# ext_rgb_M.net
KiCad netlist of a schematic drawn in EAGLE
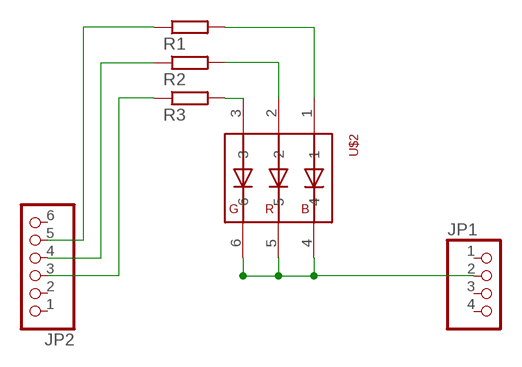
[diagram p0: schematic, sheet 1]

(export (version "E")
  (design (tool "Eeschema 10.0.6"))
  (components
    (comp (ref "JP1")
      (value "PINHD-1X4")
      (footprint "eagle-import:1X04")
      (libsource (lib "eagle-import") (part "PINHD-1X4"))
    )
    (comp (ref "JP2")
      (value "PINHD-1X6")
      (footprint "eagle-import:1X06")
      (libsource (lib "eagle-import") (part "PINHD-1X6"))
    )
    (comp (ref "R1")
      (value "R-EU_R0603")
      (footprint "eagle-import:R0603")
      (libsource (lib "eagle-import") (part "R-EU_R0603"))
    )
    (comp (ref "R2")
      (value "R-EU_R0603")
      (footprint "eagle-import:R0603")
      (libsource (lib "eagle-import") (part "R-EU_R0603"))
    )
    (comp (ref "R3")
      (value "R-EU_R0603")
      (footprint "eagle-import:R0603")
      (libsource (lib "eagle-import") (part "R-EU_R0603"))
    )
    (comp (ref "U$2")
      (value "RGB_WW-FCE50TC-Q1")
      (footprint "eagle-import:RGB_WW-FCE50TC-Q1")
      (libsource (lib "eagle-import") (part "RGB_WW-FCE50TC-Q1"))
    )
  )
  (nets
    (net (code "1") (name "Net-(JP1-Pad2)") (class "Default")
      (node (ref "JP1") (pin "2") (pinfunction "2_2") (pintype "passive"))
      (node (ref "U$2") (pin "4") (pinfunction "4_4") (pintype "bidirectional"))
      (node (ref "U$2") (pin "5") (pinfunction "5_5") (pintype "bidirectional"))
      (node (ref "U$2") (pin "6") (pinfunction "6_6") (pintype "bidirectional"))
    )
    (net (code "2") (name "Net-(JP2-Pad3)") (class "Default")
      (node (ref "JP2") (pin "3") (pinfunction "3_3") (pintype "passive"))
      (node (ref "R3") (pin "1") (pinfunction "1_1") (pintype "passive"))
    )
    (net (code "3") (name "Net-(JP2-Pad4)") (class "Default")
      (node (ref "JP2") (pin "4") (pinfunction "4_4") (pintype "passive"))
      (node (ref "R2") (pin "1") (pinfunction "1_1") (pintype "passive"))
    )
    (net (code "4") (name "Net-(JP2-Pad5)") (class "Default")
      (node (ref "JP2") (pin "5") (pinfunction "5_5") (pintype "passive"))
      (node (ref "R1") (pin "1") (pinfunction "1_1") (pintype "passive"))
    )
    (net (code "5") (name "Net-(R1-Pad2)") (class "Default")
      (node (ref "R1") (pin "2") (pinfunction "2_2") (pintype "passive"))
      (node (ref "U$2") (pin "1") (pinfunction "1_1") (pintype "bidirectional"))
    )
    (net (code "6") (name "Net-(R2-Pad2)") (class "Default")
      (node (ref "R2") (pin "2") (pinfunction "2_2") (pintype "passive"))
      (node (ref "U$2") (pin "2") (pinfunction "2_2") (pintype "bidirectional"))
    )
    (net (code "7") (name "Net-(R3-Pad2)") (class "Default")
      (node (ref "R3") (pin "2") (pinfunction "2_2") (pintype "passive"))
      (node (ref "U$2") (pin "3") (pinfunction "3_3") (pintype "bidirectional"))
    )
    (net (code "8") (name "unconnected-(JP1-Pad1)") (class "Default")
      (node (ref "JP1") (pin "1") (pinfunction "1_1") (pintype "passive"))
    )
    (net (code "9") (name "unconnected-(JP1-Pad3)") (class "Default")
      (node (ref "JP1") (pin "3") (pinfunction "3_3") (pintype "passive"))
    )
    (net (code "10") (name "unconnected-(JP1-Pad4)") (class "Default")
      (node (ref "JP1") (pin "4") (pinfunction "4_4") (pintype "passive"))
    )
    (net (code "11") (name "unconnected-(JP2-Pad1)") (class "Default")
      (node (ref "JP2") (pin "1") (pinfunction "1_1") (pintype "passive"))
    )
    (net (code "12") (name "unconnected-(JP2-Pad2)") (class "Default")
      (node (ref "JP2") (pin "2") (pinfunction "2_2") (pintype "passive"))
    )
    (net (code "13") (name "unconnected-(JP2-Pad6)") (class "Default")
      (node (ref "JP2") (pin "6") (pinfunction "6_6") (pintype "passive"))
    )
  )
)
